# Power_Supply.net
KiCad netlist of a schematic drawn in Altium Designer
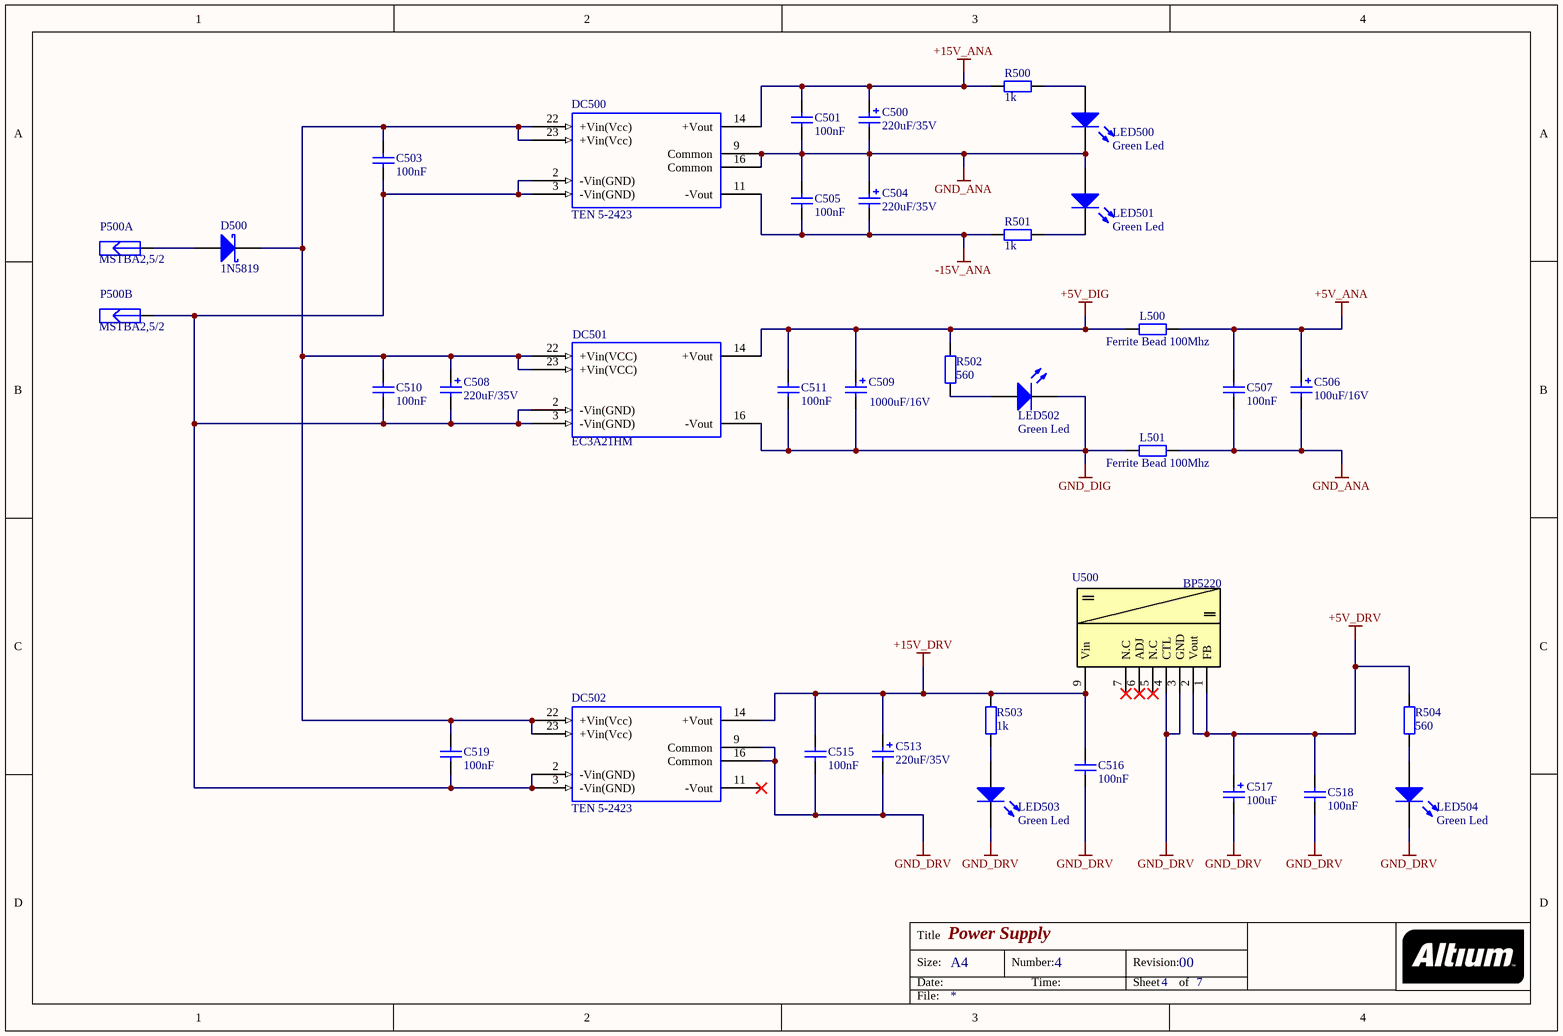
[diagram p0: Power Supply.SchDoc]

(export (version "E")
  (design (tool "Eeschema 10.0.6"))
  (components
    (comp (ref "C500")
      (value "220uF/35V")
      (footprint "CAPPR3.5-8x12")
      (fields (field (name "Comment") "Cap"))
      (libsource (lib "Capacitors") (part "Cap pol"))
    )
    (comp (ref "C501")
      (value "100nF")
      (footprint "1206_REFLOW")
      (fields (field (name "Comment") "Cap 1206"))
      (libsource (lib "Capacitors") (part "Cap 1206"))
    )
    (comp (ref "C503")
      (value "100nF")
      (footprint "1206_REFLOW")
      (fields (field (name "Comment") "Cap 1206"))
      (libsource (lib "Capacitors") (part "Cap 1206"))
    )
    (comp (ref "C504")
      (value "220uF/35V")
      (footprint "CAPPR3.5-8x12")
      (fields (field (name "Comment") "Cap"))
      (libsource (lib "Capacitors") (part "Cap pol"))
    )
    (comp (ref "C505")
      (value "100nF")
      (footprint "1206_REFLOW")
      (fields (field (name "Comment") "Cap 1206"))
      (libsource (lib "Capacitors") (part "Cap 1206"))
    )
    (comp (ref "C506")
      (value "100uF/16V")
      (footprint "CAPPR3.5-8x12")
      (fields (field (name "Comment") "Cap"))
      (libsource (lib "Capacitors") (part "Cap pol"))
    )
    (comp (ref "C507")
      (value "100nF")
      (footprint "1206_REFLOW")
      (fields (field (name "Comment") "Cap 1206"))
      (libsource (lib "Capacitors") (part "Cap 1206"))
    )
    (comp (ref "C508")
      (value "220uF/35V")
      (footprint "CAPPR3.5-8x12")
      (fields (field (name "Comment") "Cap"))
      (libsource (lib "Capacitors") (part "Cap pol"))
    )
    (comp (ref "C509")
      (value "1000uF/16V")
      (footprint "CAPPR3.5-8x12")
      (fields (field (name "Comment") "Cap"))
      (libsource (lib "Capacitors") (part "Cap pol"))
    )
    (comp (ref "C510")
      (value "100nF")
      (footprint "1206_REFLOW")
      (fields (field (name "Comment") "Cap 1206"))
      (libsource (lib "Capacitors") (part "Cap 1206"))
    )
    (comp (ref "C511")
      (value "100nF")
      (footprint "1206_REFLOW")
      (fields (field (name "Comment") "Cap 1206"))
      (libsource (lib "Capacitors") (part "Cap 1206"))
    )
    (comp (ref "C513")
      (value "220uF/35V")
      (footprint "CAPPR3.5-8x12")
      (fields (field (name "Comment") "Cap"))
      (libsource (lib "Capacitors") (part "Cap pol"))
    )
    (comp (ref "C515")
      (value "100nF")
      (footprint "1206_REFLOW")
      (fields (field (name "Comment") "Cap 1206"))
      (libsource (lib "Capacitors") (part "Cap 1206"))
    )
    (comp (ref "C516")
      (value "100nF")
      (footprint "1206_REFLOW")
      (fields (field (name "Comment") "Cap 1206"))
      (libsource (lib "Capacitors") (part "Cap 1206"))
    )
    (comp (ref "C517")
      (value "100uF")
      (footprint "CAPPR3.5-8x12")
      (fields (field (name "Comment") "Cap"))
      (libsource (lib "Capacitors") (part "Cap pol"))
    )
    (comp (ref "C518")
      (value "100nF")
      (footprint "1206_REFLOW")
      (fields (field (name "Comment") "Cap 1206"))
      (libsource (lib "Capacitors") (part "Cap 1206"))
    )
    (comp (ref "C519")
      (value "100nF")
      (footprint "1206_REFLOW")
      (fields (field (name "Comment") "Cap 1206"))
      (libsource (lib "Capacitors") (part "Cap 1206"))
    )
    (comp (ref "D500")
      (value "1N5819")
      (footprint "DO-214_S1A(Primary)")
      (libsource (lib "Diode") (part "1N5819"))
    )
    (comp (ref "DC500")
      (value "TEN 5-2423")
      (footprint "DIP24_TRACO")
      (libsource (lib "DC-DC") (part "TEN 5-2423"))
    )
    (comp (ref "DC501")
      (value "EC3A21HM")
      (footprint "DIP24_TRACO")
      (description "DC/DC CONVERTER, 3W 5V")
      (fields (field (name "MANUFACTURER") "CINCON"))
      (libsource (lib "DC-DC") (part "EC3A21HM"))
    )
    (comp (ref "DC502")
      (value "TEN 5-2423")
      (footprint "DIP24_TRACO")
      (libsource (lib "DC-DC") (part "TEN 5-2423"))
    )
    (comp (ref "L500")
      (value "Ferrite Bead 100Mhz")
      (footprint "3216[1206]")
      (fields (field (name "Comment") "RES"))
      (libsource (lib "Resistor") (part "RES 1"))
    )
    (comp (ref "L501")
      (value "Ferrite Bead 100Mhz")
      (footprint "3216[1206]")
      (fields (field (name "Comment") "RES"))
      (libsource (lib "Resistor") (part "RES 1"))
    )
    (comp (ref "LED500") (value "Green Led") (footprint "LED_1206") (libsource (lib "LED") (part "LED")))
    (comp (ref "LED501") (value "Green Led") (footprint "LED_1206") (libsource (lib "LED") (part "LED")))
    (comp (ref "LED502") (value "Green Led") (footprint "LED_1206") (libsource (lib "LED") (part "LED")))
    (comp (ref "LED503") (value "Green Led") (footprint "LED_1206") (libsource (lib "LED") (part "LED")))
    (comp (ref "LED504") (value "Green Led") (footprint "LED_1206") (libsource (lib "LED") (part "LED")))
    (comp (ref "P500")
      (value "MSTBA2,5/2")
      (footprint "MSTB2.5/2-G-5.08")
      (description "Header, right angled, 12 A, 250 V, pitch 5.08 mm, No. of poles:2")
      (fields (field (name "MANUFACTURER") "Phoenix") (field (name "MFRR. PART NO.") "1757242"))
      (libsource (lib "Connector") (part "MSTBA 2,5/ 2-G-5,08"))
    )
    (comp (ref "R500")
      (value "1k")
      (footprint "1206_REFLOW")
      (fields (field (name "Comment") "RES"))
      (libsource (lib "") (part "RES 1_1"))
    )
    (comp (ref "R501")
      (value "1k")
      (footprint "1206_REFLOW")
      (fields (field (name "Comment") "RES"))
      (libsource (lib "") (part "RES 1_1"))
    )
    (comp (ref "R502")
      (value "560")
      (footprint "1206_REFLOW")
      (fields (field (name "Comment") "RES"))
      (libsource (lib "") (part "RES 1_2"))
    )
    (comp (ref "R503")
      (value "1k")
      (footprint "1206_REFLOW")
      (fields (field (name "Comment") "RES"))
      (libsource (lib "") (part "RES 1_2"))
    )
    (comp (ref "R504")
      (value "560")
      (footprint "1206_REFLOW")
      (fields (field (name "Comment") "RES"))
      (libsource (lib "") (part "RES 1_2"))
    )
    (comp (ref "U500")
      (value "BP5220")
      (footprint "BP5220")
      (fields (field (name "Comment") "DC DC ROHM"))
      (libsource (lib "DC-DC") (part "BP5220"))
    )
  )
  (nets
    (net (code "1") (name "+5V_ANA") (class "Default")
      (node (ref "C506") (pin "1") (pinfunction "1_1") (pintype "passive"))
      (node (ref "C507") (pin "2") (pinfunction "2_2") (pintype "passive"))
      (node (ref "L500") (pin "2") (pinfunction "2_2") (pintype "passive"))
    )
    (net (code "2") (name "+5V_DIG") (class "Default")
      (node (ref "C509") (pin "1") (pinfunction "1_1") (pintype "passive"))
      (node (ref "C511") (pin "2") (pinfunction "2_2") (pintype "passive"))
      (node (ref "DC501") (pin "14") (pinfunction "+Vout_14") (pintype "power_in"))
      (node (ref "L500") (pin "1") (pinfunction "1_1") (pintype "passive"))
      (node (ref "R502") (pin "1") (pinfunction "1_1") (pintype "passive"))
    )
    (net (code "3") (name "+5V_DRV") (class "Default")
      (node (ref "C517") (pin "1") (pinfunction "1_1") (pintype "passive"))
      (node (ref "C518") (pin "2") (pinfunction "2_2") (pintype "passive"))
      (node (ref "R504") (pin "1") (pinfunction "1_1") (pintype "passive"))
      (node (ref "U500") (pin "1") (pinfunction "FB_1") (pintype "passive"))
      (node (ref "U500") (pin "2") (pinfunction "Vout_2") (pintype "passive"))
    )
    (net (code "4") (name "+15V_ANA") (class "Default")
      (node (ref "C500") (pin "1") (pinfunction "1_1") (pintype "passive"))
      (node (ref "C501") (pin "2") (pinfunction "2_2") (pintype "passive"))
      (node (ref "DC500") (pin "14") (pinfunction "+Vout_14") (pintype "power_in"))
      (node (ref "R500") (pin "2") (pinfunction "2_2") (pintype "passive"))
    )
    (net (code "5") (name "+15V_DRV") (class "Default")
      (node (ref "C513") (pin "1") (pinfunction "1_1") (pintype "passive"))
      (node (ref "C515") (pin "2") (pinfunction "2_2") (pintype "passive"))
      (node (ref "C516") (pin "2") (pinfunction "2_2") (pintype "passive"))
      (node (ref "DC502") (pin "14") (pinfunction "+Vout_14") (pintype "power_in"))
      (node (ref "R503") (pin "1") (pinfunction "1_1") (pintype "passive"))
      (node (ref "U500") (pin "9") (pinfunction "Vin_9") (pintype "passive"))
    )
    (net (code "6") (name "-15V_ANA") (class "Default")
      (node (ref "C504") (pin "2") (pinfunction "2_2") (pintype "passive"))
      (node (ref "C505") (pin "1") (pinfunction "1_1") (pintype "passive"))
      (node (ref "DC500") (pin "11") (pinfunction "-Vout_11") (pintype "power_in"))
      (node (ref "R501") (pin "2") (pinfunction "2_2") (pintype "passive"))
    )
    (net (code "7") (name "GND_ANA") (class "Default")
      (node (ref "C500") (pin "2") (pinfunction "2_2") (pintype "passive"))
      (node (ref "C501") (pin "1") (pinfunction "1_1") (pintype "passive"))
      (node (ref "C504") (pin "1") (pinfunction "1_1") (pintype "passive"))
      (node (ref "C505") (pin "2") (pinfunction "2_2") (pintype "passive"))
      (node (ref "C506") (pin "2") (pinfunction "2_2") (pintype "passive"))
      (node (ref "C507") (pin "1") (pinfunction "1_1") (pintype "passive"))
      (node (ref "DC500") (pin "16") (pinfunction "Common_16") (pintype "power_in"))
      (node (ref "DC500") (pin "9") (pinfunction "Common_9") (pintype "passive"))
      (node (ref "L501") (pin "2") (pinfunction "2_2") (pintype "passive"))
      (node (ref "LED500") (pin "K") (pinfunction "K_K") (pintype "passive"))
      (node (ref "LED501") (pin "A") (pinfunction "A_A") (pintype "passive"))
    )
    (net (code "8") (name "GND_DIG") (class "Default")
      (node (ref "C509") (pin "2") (pinfunction "2_2") (pintype "passive"))
      (node (ref "C511") (pin "1") (pinfunction "1_1") (pintype "passive"))
      (node (ref "DC501") (pin "16") (pinfunction "-Vout_16") (pintype "power_in"))
      (node (ref "L501") (pin "1") (pinfunction "1_1") (pintype "passive"))
      (node (ref "LED502") (pin "K") (pinfunction "K_K") (pintype "passive"))
    )
    (net (code "9") (name "GND_DRV") (class "Default")
      (node (ref "C513") (pin "2") (pinfunction "2_2") (pintype "passive"))
      (node (ref "C515") (pin "1") (pinfunction "1_1") (pintype "passive"))
      (node (ref "C516") (pin "1") (pinfunction "1_1") (pintype "passive"))
      (node (ref "C517") (pin "2") (pinfunction "2_2") (pintype "passive"))
      (node (ref "C518") (pin "1") (pinfunction "1_1") (pintype "passive"))
      (node (ref "DC502") (pin "16") (pinfunction "Common_16") (pintype "power_in"))
      (node (ref "DC502") (pin "9") (pinfunction "Common_9") (pintype "passive"))
      (node (ref "LED503") (pin "K") (pinfunction "K_K") (pintype "passive"))
      (node (ref "LED504") (pin "K") (pinfunction "K_K") (pintype "passive"))
      (node (ref "U500") (pin "3") (pinfunction "GND_3") (pintype "passive"))
      (node (ref "U500") (pin "4") (pinfunction "CTL_4") (pintype "passive"))
    )
    (net (code "10") (name "Net-(C503-Pad2)") (class "Default")
      (node (ref "C503") (pin "2") (pinfunction "2_2") (pintype "passive"))
      (node (ref "C508") (pin "1") (pinfunction "1_1") (pintype "passive"))
      (node (ref "C510") (pin "2") (pinfunction "2_2") (pintype "passive"))
      (node (ref "C519") (pin "2") (pinfunction "2_2") (pintype "passive"))
      (node (ref "D500") (pin "K") (pinfunction "K_K") (pintype "passive"))
      (node (ref "DC500") (pin "22") (pinfunction "+Vin(Vcc)_22") (pintype "input"))
      (node (ref "DC500") (pin "23") (pinfunction "+Vin(Vcc)_23") (pintype "input"))
      (node (ref "DC501") (pin "22") (pinfunction "+Vin(VCC)_22") (pintype "input"))
      (node (ref "DC501") (pin "23") (pinfunction "+Vin(VCC)_23") (pintype "input"))
      (node (ref "DC502") (pin "22") (pinfunction "+Vin(Vcc)_22") (pintype "input"))
      (node (ref "DC502") (pin "23") (pinfunction "+Vin(Vcc)_23") (pintype "input"))
    )
    (net (code "11") (name "Net-(LED500-PadA)") (class "Default")
      (node (ref "LED500") (pin "A") (pinfunction "A_A") (pintype "passive"))
      (node (ref "R500") (pin "1") (pinfunction "1_1") (pintype "passive"))
    )
    (net (code "12") (name "Net-(LED501-PadK)") (class "Default")
      (node (ref "LED501") (pin "K") (pinfunction "K_K") (pintype "passive"))
      (node (ref "R501") (pin "1") (pinfunction "1_1") (pintype "passive"))
    )
    (net (code "13") (name "Net-(LED502-PadA)") (class "Default")
      (node (ref "LED502") (pin "A") (pinfunction "A_A") (pintype "passive"))
      (node (ref "R502") (pin "2") (pinfunction "2_2") (pintype "passive"))
    )
    (net (code "14") (name "Net-(LED503-PadA)") (class "Default")
      (node (ref "LED503") (pin "A") (pinfunction "A_A") (pintype "passive"))
      (node (ref "R503") (pin "2") (pinfunction "2_2") (pintype "passive"))
    )
    (net (code "15") (name "Net-(LED504-PadA)") (class "Default")
      (node (ref "LED504") (pin "A") (pinfunction "A_A") (pintype "passive"))
      (node (ref "R504") (pin "2") (pinfunction "2_2") (pintype "passive"))
    )
    (net (code "16") (name "Net-(P500A-SIG)") (class "Default")
      (node (ref "D500") (pin "A") (pinfunction "A_A") (pintype "passive"))
      (node (ref "P500") (pin "1") (pinfunction "SIG_1") (pintype "passive"))
    )
    (net (code "17") (name "Net-(P500B-SIG)") (class "Default")
      (node (ref "C503") (pin "1") (pinfunction "1_1") (pintype "passive"))
      (node (ref "C508") (pin "2") (pinfunction "2_2") (pintype "passive"))
      (node (ref "C510") (pin "1") (pinfunction "1_1") (pintype "passive"))
      (node (ref "C519") (pin "1") (pinfunction "1_1") (pintype "passive"))
      (node (ref "DC500") (pin "2") (pinfunction "-Vin(GND)_2") (pintype "input"))
      (node (ref "DC500") (pin "3") (pinfunction "-Vin(GND)_3") (pintype "input"))
      (node (ref "DC501") (pin "2") (pinfunction "-Vin(GND)_2") (pintype "input"))
      (node (ref "DC501") (pin "3") (pinfunction "-Vin(GND)_3") (pintype "input"))
      (node (ref "DC502") (pin "2") (pinfunction "-Vin(GND)_2") (pintype "input"))
      (node (ref "DC502") (pin "3") (pinfunction "-Vin(GND)_3") (pintype "input"))
      (node (ref "P500") (pin "2") (pinfunction "SIG_2") (pintype "passive"))
    )
    (net (code "18") (name "unconnected-(DC502--Vout-Pad11)") (class "Default")
      (node (ref "DC502") (pin "11") (pinfunction "-Vout_11") (pintype "power_in+no_connect"))
    )
    (net (code "19") (name "unconnected-(U500-ADJ-Pad6)") (class "Default")
      (node (ref "U500") (pin "6") (pinfunction "ADJ_6") (pintype "passive+no_connect"))
    )
    (net (code "20") (name "unconnected-(U500-N.C-Pad5)") (class "Default")
      (node (ref "U500") (pin "5") (pinfunction "N.C_5") (pintype "passive+no_connect"))
    )
    (net (code "21") (name "unconnected-(U500-N.C-Pad7)") (class "Default")
      (node (ref "U500") (pin "7") (pinfunction "N.C_7") (pintype "passive+no_connect"))
    )
  )
)
